# FR4_Power_Divider.net
KiCad netlist of a schematic drawn in Altium Designer
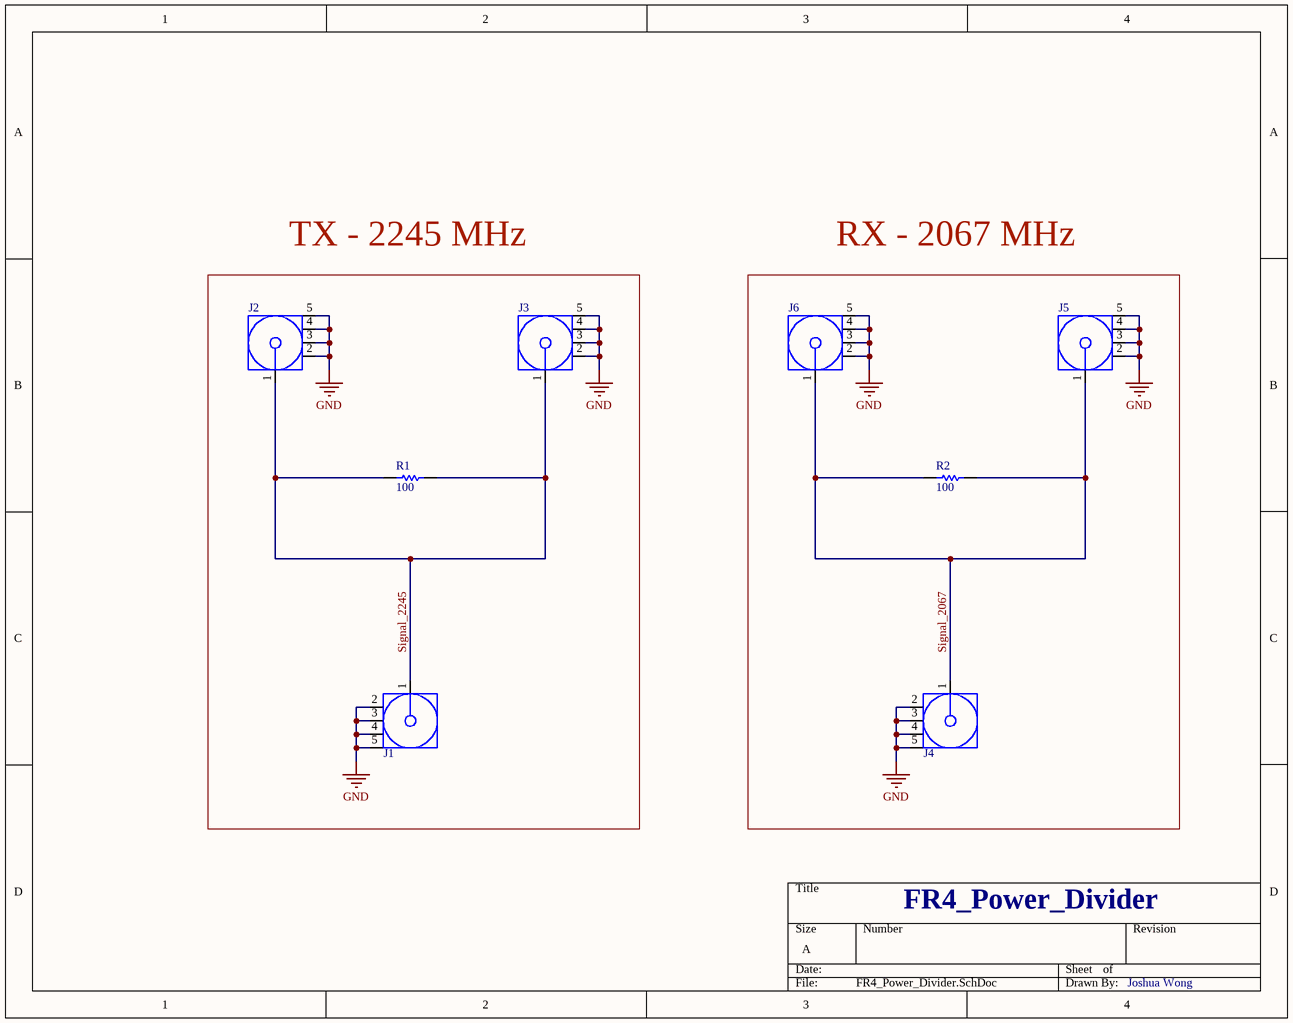
[diagram p0: FR4_Power_Divider.SchDoc]

(export (version "E")
  (design (tool "Eeschema 10.0.6"))
  (components
    (comp (ref "J1")
      (value "0732511150")
      (footprint "FP-0732511150-MFG")
      (description "RF SMA Connector, 1 Contact(s), Board Mount, Surface Mount Terminal, Locking")
      (libsource (lib "University of Toronto Aerospace Team") (part "COAX-F"))
    )
    (comp (ref "J2")
      (value "0732511150")
      (footprint "FP-0732511150-MFG")
      (description "RF SMA Connector, 1 Contact(s), Board Mount, Surface Mount Terminal, Locking")
      (libsource (lib "University of Toronto Aerospace Team") (part "COAX-F"))
    )
    (comp (ref "J3")
      (value "0732511150")
      (footprint "FP-0732511150-MFG")
      (description "RF SMA Connector, 1 Contact(s), Board Mount, Surface Mount Terminal, Locking")
      (libsource (lib "University of Toronto Aerospace Team") (part "COAX-F"))
    )
    (comp (ref "J4")
      (value "0732511150")
      (footprint "FP-0732511150-MFG")
      (description "RF SMA Connector, 1 Contact(s), Board Mount, Surface Mount Terminal, Locking")
      (libsource (lib "University of Toronto Aerospace Team") (part "COAX-F"))
    )
    (comp (ref "J5")
      (value "0732511150")
      (footprint "FP-0732511150-MFG")
      (description "RF SMA Connector, 1 Contact(s), Board Mount, Surface Mount Terminal, Locking")
      (libsource (lib "University of Toronto Aerospace Team") (part "COAX-F"))
    )
    (comp (ref "J6")
      (value "0732511150")
      (footprint "FP-0732511150-MFG")
      (description "RF SMA Connector, 1 Contact(s), Board Mount, Surface Mount Terminal, Locking")
      (libsource (lib "University of Toronto Aerospace Team") (part "COAX-F"))
    )
    (comp (ref "R1")
      (value "100")
      (footprint "RES0402R")
      (description "RES SMD 100 OHM 1% 1/16W 0402")
      (fields (field (name "MANUFACTURER") "Vishay Dale") (field (name "TOLERANCE") "1%"))
      (libsource (lib "University of Toronto Aerospace Team") (part "Res-2"))
    )
    (comp (ref "R2")
      (value "100")
      (footprint "RES0402R")
      (description "RES SMD 100 OHM 1% 1/16W 0402")
      (fields (field (name "MANUFACTURER") "Vishay Dale") (field (name "TOLERANCE") "1%"))
      (libsource (lib "University of Toronto Aerospace Team") (part "Res-2"))
    )
  )
  (nets
    (net (code "1") (name "/Signal_2067") (class "Default")
      (node (ref "J4") (pin "1") (pinfunction "Signal_1") (pintype "passive"))
      (node (ref "J5") (pin "1") (pinfunction "Signal_1") (pintype "passive"))
      (node (ref "J6") (pin "1") (pinfunction "Signal_1") (pintype "passive"))
      (node (ref "R2") (pin "1") (pinfunction "1_1") (pintype "passive"))
      (node (ref "R2") (pin "2") (pinfunction "2_2") (pintype "passive"))
    )
    (net (code "2") (name "/Signal_2245") (class "Default")
      (node (ref "J1") (pin "1") (pinfunction "Signal_1") (pintype "passive"))
      (node (ref "J2") (pin "1") (pinfunction "Signal_1") (pintype "passive"))
      (node (ref "J3") (pin "1") (pinfunction "Signal_1") (pintype "passive"))
      (node (ref "R1") (pin "1") (pinfunction "1_1") (pintype "passive"))
      (node (ref "R1") (pin "2") (pinfunction "2_2") (pintype "passive"))
    )
    (net (code "3") (name "GND") (class "Default")
      (node (ref "J1") (pin "2") (pinfunction "GND_2") (pintype "power_in"))
      (node (ref "J1") (pin "3") (pinfunction "GND_3") (pintype "power_in"))
      (node (ref "J1") (pin "4") (pinfunction "GND_4") (pintype "power_in"))
      (node (ref "J1") (pin "5") (pinfunction "GND_5") (pintype "power_in"))
      (node (ref "J2") (pin "2") (pinfunction "GND_2") (pintype "power_in"))
      (node (ref "J2") (pin "3") (pinfunction "GND_3") (pintype "power_in"))
      (node (ref "J2") (pin "4") (pinfunction "GND_4") (pintype "power_in"))
      (node (ref "J2") (pin "5") (pinfunction "GND_5") (pintype "power_in"))
      (node (ref "J3") (pin "2") (pinfunction "GND_2") (pintype "power_in"))
      (node (ref "J3") (pin "3") (pinfunction "GND_3") (pintype "power_in"))
      (node (ref "J3") (pin "4") (pinfunction "GND_4") (pintype "power_in"))
      (node (ref "J3") (pin "5") (pinfunction "GND_5") (pintype "power_in"))
      (node (ref "J4") (pin "2") (pinfunction "GND_2") (pintype "power_in"))
      (node (ref "J4") (pin "3") (pinfunction "GND_3") (pintype "power_in"))
      (node (ref "J4") (pin "4") (pinfunction "GND_4") (pintype "power_in"))
      (node (ref "J4") (pin "5") (pinfunction "GND_5") (pintype "power_in"))
      (node (ref "J5") (pin "2") (pinfunction "GND_2") (pintype "power_in"))
      (node (ref "J5") (pin "3") (pinfunction "GND_3") (pintype "power_in"))
      (node (ref "J5") (pin "4") (pinfunction "GND_4") (pintype "power_in"))
      (node (ref "J5") (pin "5") (pinfunction "GND_5") (pintype "power_in"))
      (node (ref "J6") (pin "2") (pinfunction "GND_2") (pintype "power_in"))
      (node (ref "J6") (pin "3") (pinfunction "GND_3") (pintype "power_in"))
      (node (ref "J6") (pin "4") (pinfunction "GND_4") (pintype "power_in"))
      (node (ref "J6") (pin "5") (pinfunction "GND_5") (pintype "power_in"))
    )
  )
)
